# SCH_NFC-Card-Ayra_2024-10-10.net
KiCad netlist of a schematic drawn in EasyEDA
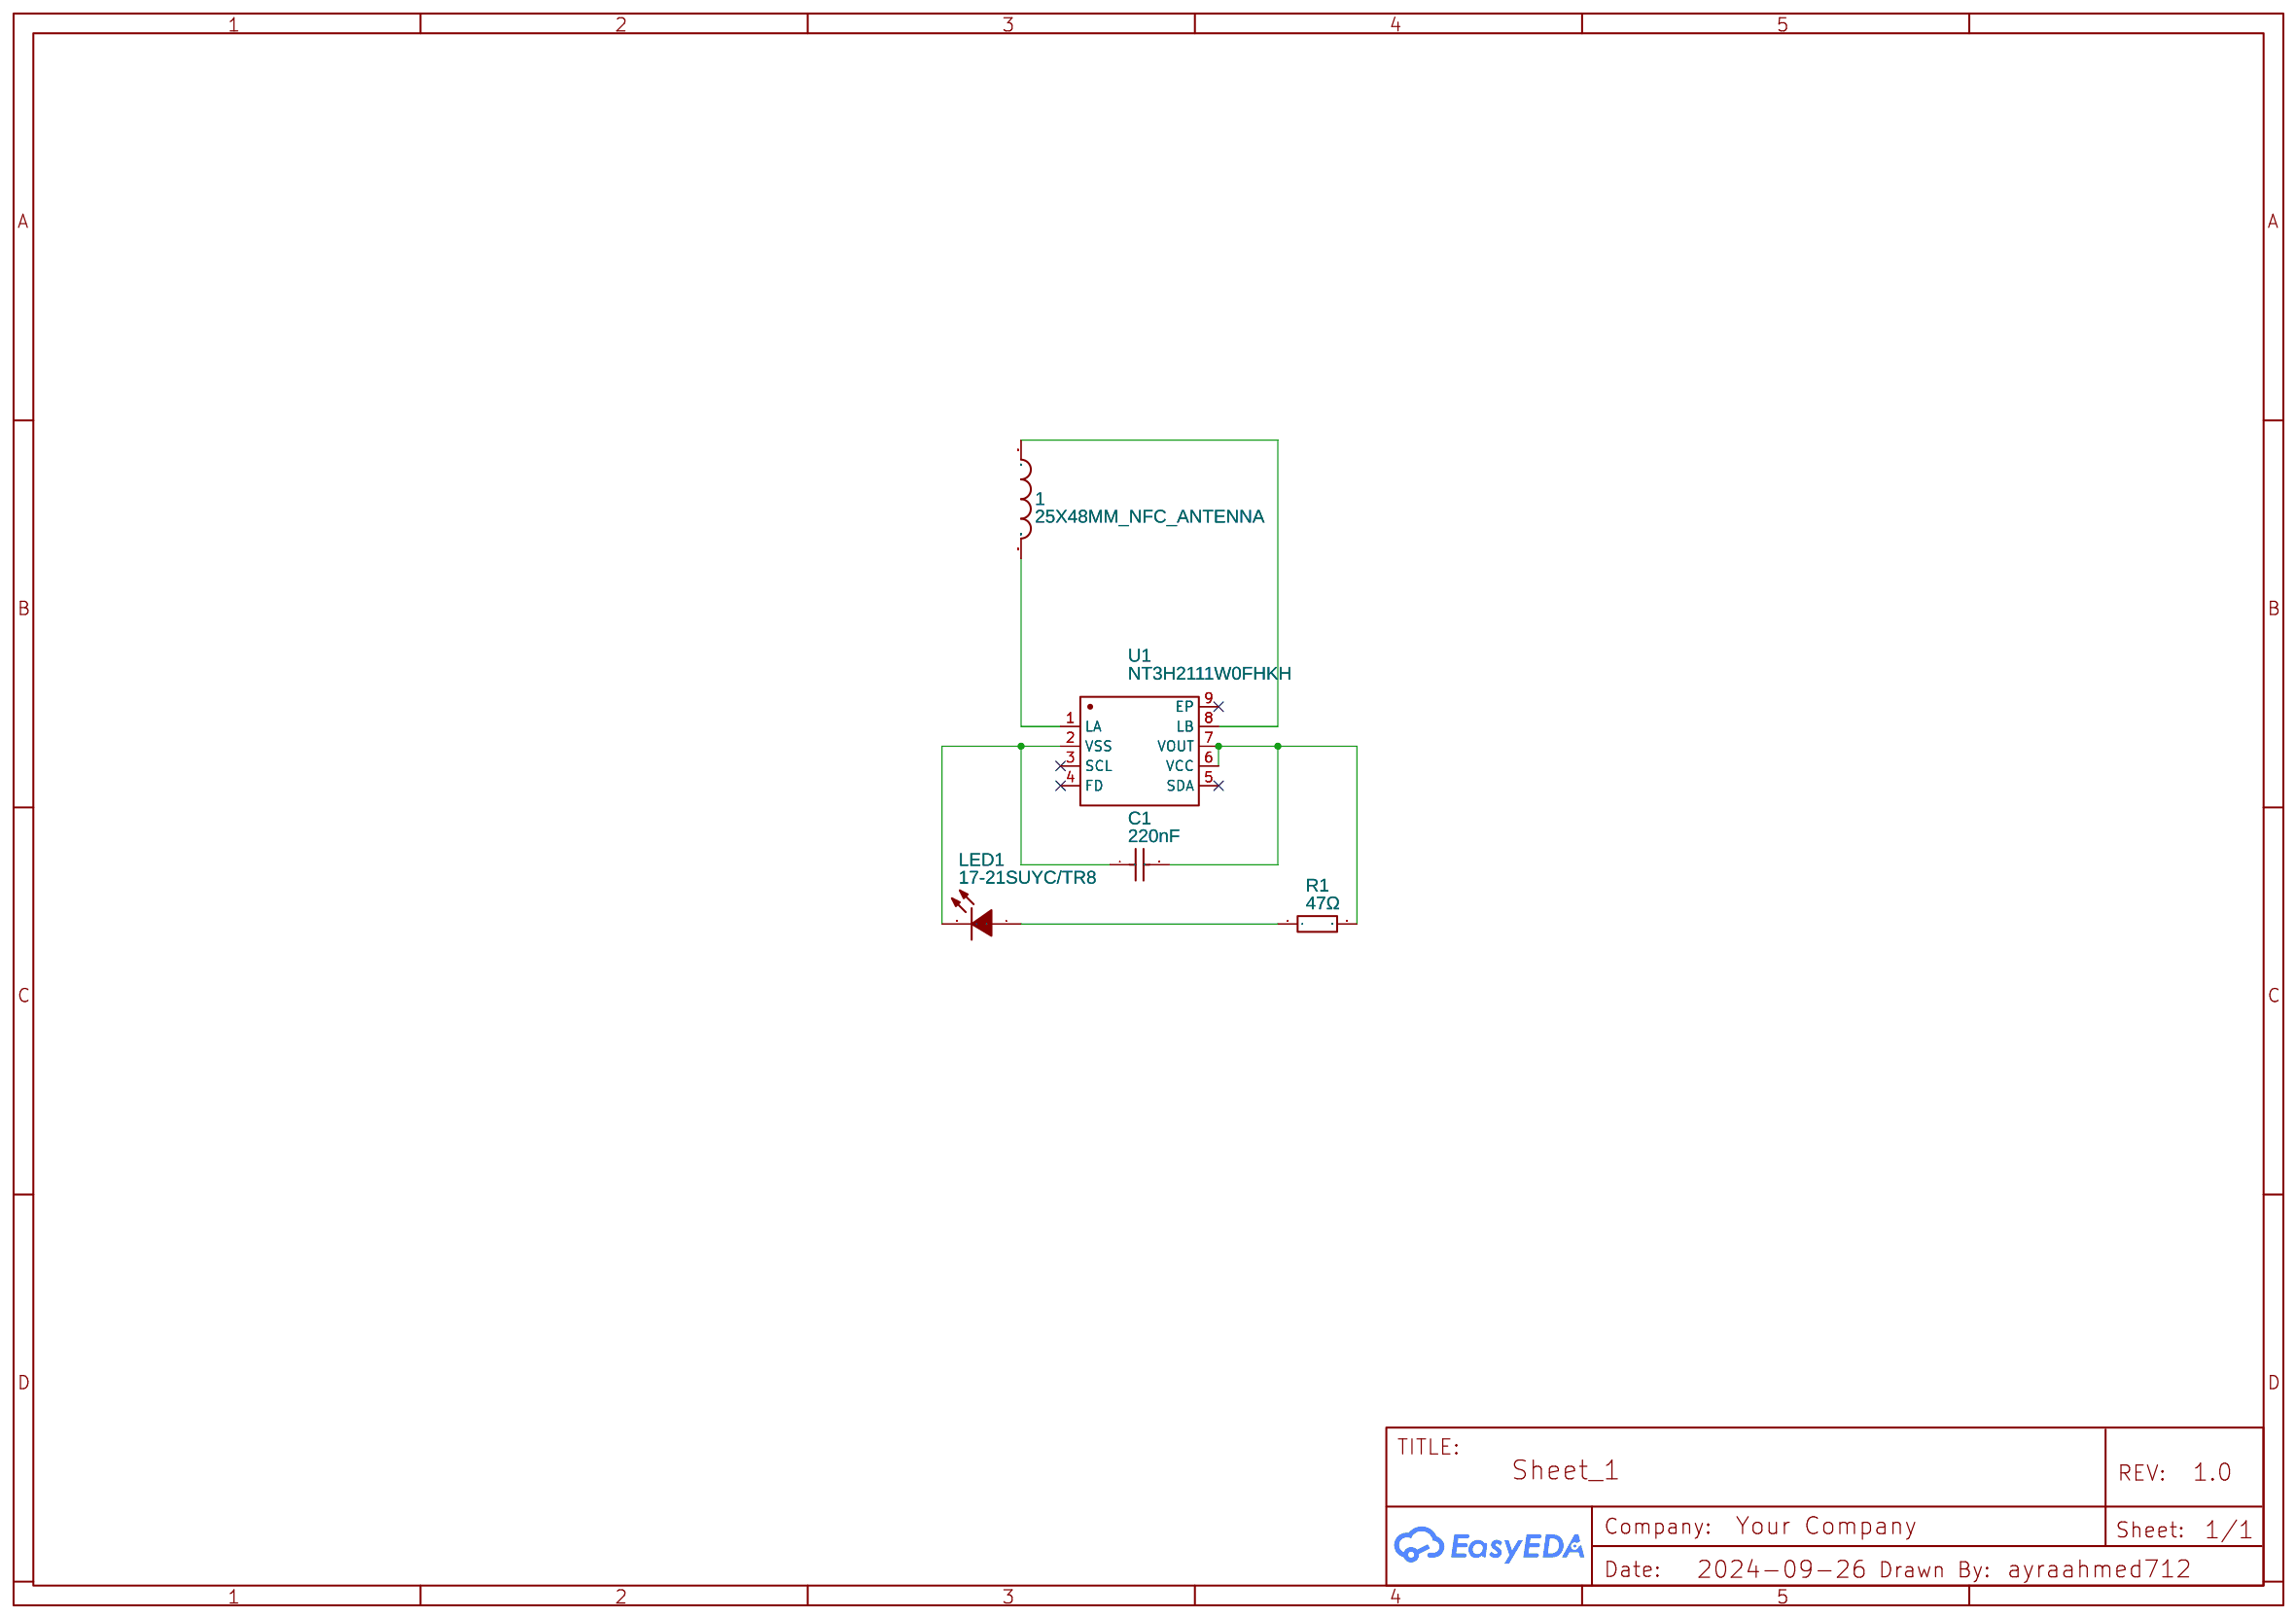
[diagram p0: schematic sheet]

(export (version "E")
  (design (tool "Eeschema 10.0.6"))
  (components
    (comp (ref "1") (value "25X48MM_NFC_ANTENNA") (libsource (lib "") (part "25X48MM_NFC_ANTENNA")))
    (comp (ref "C1")
      (value "220nF")
      (fields
        (field (name "Manufacturer Part") "CL10B224KA8NNNC")
        (field (name "Manufacturer") "SAMSUNG(三星)")
      )
      (libsource (lib "") (part "CL10B224KA8NNNC"))
    )
    (comp (ref "LED1")
      (value "17-21SUYC/TR8")
      (fields (field (name "Manufacturer Part") "KT-0805黄灯") (field (name "Manufacturer") "KENTO"))
      (libsource (lib "") (part "17-21SUYC/TR8"))
    )
    (comp (ref "R1")
      (value "47Ω")
      (fields
        (field (name "Manufacturer Part") "0603WAF470JT5E")
        (field (name "Manufacturer") "UNI-ROYAL(厚声)")
      )
      (libsource (lib "") (part "0603WAF470JT5E"))
    )
    (comp (ref "U1")
      (value "NT3H2111W0FHKH")
      (fields (field (name "Manufacturer") "NXP(恩智浦)"))
      (libsource (lib "") (part "NT3H2111W0FHKH"))
    )
  )
  (nets
    (net (code "1") (name "Net-(LED1-+)") (class "Default")
      (node (ref "LED1") (pin "1") (pinfunction "+_1") (pintype "unspecified"))
      (node (ref "R1") (pin "1") (pinfunction "1_1") (pintype "input"))
    )
    (net (code "2") (name "Net-(LED1--)") (class "Default")
      (node (ref "C1") (pin "1") (pinfunction "1_1") (pintype "input"))
      (node (ref "LED1") (pin "2") (pinfunction "-_2") (pintype "unspecified"))
      (node (ref "U1") (pin "2") (pinfunction "VSS_2") (pintype "unspecified"))
    )
    (net (code "3") (name "Net-(U1-LA)") (class "Default")
      (node (ref "1") (pin "P$2") (pinfunction "P$2_P$2") (pintype "bidirectional"))
      (node (ref "U1") (pin "1") (pinfunction "LA_1") (pintype "unspecified"))
    )
    (net (code "4") (name "Net-(U1-LB)") (class "Default")
      (node (ref "1") (pin "P$1") (pinfunction "P$1_P$1") (pintype "bidirectional"))
      (node (ref "U1") (pin "8") (pinfunction "LB_8") (pintype "unspecified"))
    )
    (net (code "5") (name "Net-(U1-VCC)") (class "Default")
      (node (ref "C1") (pin "2") (pinfunction "2_2") (pintype "input"))
      (node (ref "R1") (pin "2") (pinfunction "2_2") (pintype "input"))
      (node (ref "U1") (pin "6") (pinfunction "VCC_6") (pintype "unspecified"))
      (node (ref "U1") (pin "7") (pinfunction "VOUT_7") (pintype "unspecified"))
    )
    (net (code "6") (name "unconnected-(U1-EP-Pad9)") (class "Default")
      (node (ref "U1") (pin "9") (pinfunction "EP_9") (pintype "unspecified+no_connect"))
    )
    (net (code "7") (name "unconnected-(U1-FD-Pad4)") (class "Default")
      (node (ref "U1") (pin "4") (pinfunction "FD_4") (pintype "unspecified+no_connect"))
    )
    (net (code "8") (name "unconnected-(U1-SCL-Pad3)") (class "Default")
      (node (ref "U1") (pin "3") (pinfunction "SCL_3") (pintype "unspecified+no_connect"))
    )
    (net (code "9") (name "unconnected-(U1-SDA-Pad5)") (class "Default")
      (node (ref "U1") (pin "5") (pinfunction "SDA_5") (pintype "unspecified+no_connect"))
    )
  )
)
